# DB10005_CAN.net
KiCad netlist of a schematic drawn in Altium Designer
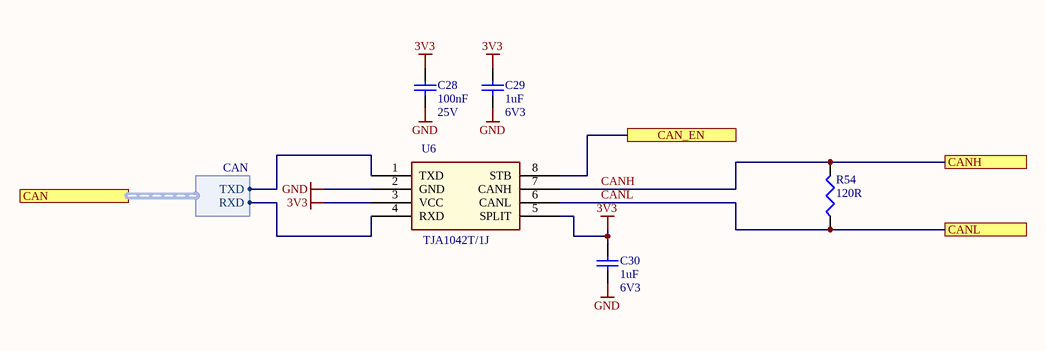
[diagram p0: DB10005_CAN.SchDoc]

(export (version "E")
  (design (tool "Eeschema 10.0.6"))
  (components
    (comp (ref "C28")
      (value "100nF")
      (footprint "C0402")
      (description "Capacitor, 100nF, 25V, X7R")
      (fields (field (name "VOLTAGE RATING") "25V"))
      (libsource (lib "AR_Capacitors_Ceramic") (part "100nF/0402/CER/25V"))
    )
    (comp (ref "C29")
      (value "1uF")
      (footprint "C0402")
      (description "Capacitor, 1uF, 6.3V, X5R")
      (fields (field (name "VOLTAGE RATING") "6V3"))
      (libsource (lib "AR_Capacitors_Ceramic") (part "1uF/0402/CER/6.3V"))
    )
    (comp (ref "C30")
      (value "1uF")
      (footprint "C0402")
      (description "Capacitor, 1uF, 6.3V, X5R")
      (fields (field (name "VOLTAGE RATING") "6V3"))
      (libsource (lib "AR_Capacitors_Ceramic") (part "1uF/0402/CER/6.3V"))
    )
    (comp (ref "R54")
      (value "120R")
      (footprint "0805")
      (description "Resistor, 0R, 0.1%, 0.1W, 150V, 200PPM, 0805")
      (libsource (lib "AR_Resistors_SMD") (part "0/0805/0100W/150V"))
    )
    (comp (ref "U6")
      (value "TJA1042T/1J")
      (footprint "SOP-8")
      (libsource (lib "DB10005_DieBieMS") (part "TJA1042T/1J"))
    )
  )
  (nets
    (net (code "2") (name "/CANH") (class "Default")
      (node (ref "R54") (pin "2") (pinfunction "2_2") (pintype "passive"))
      (node (ref "U6") (pin "7") (pinfunction "CANH_7") (pintype "passive"))
    )
    (net (code "3") (name "/CANL") (class "Default")
      (node (ref "R54") (pin "1") (pinfunction "1_1") (pintype "passive"))
      (node (ref "U6") (pin "6") (pinfunction "CANL_6") (pintype "passive"))
    )
    (net (code "4") (name "/CAN_EN") (class "Default")
      (node (ref "U6") (pin "8") (pinfunction "STB_8") (pintype "passive"))
    )
    (net (code "5") (name "/RXD") (class "Default")
      (node (ref "U6") (pin "4") (pinfunction "RXD_4") (pintype "passive"))
    )
    (net (code "6") (name "/TXD") (class "Default")
      (node (ref "U6") (pin "1") (pinfunction "TXD_1") (pintype "passive"))
    )
    (net (code "8") (name "3V3") (class "Default")
      (node (ref "C28") (pin "2") (pinfunction "2_2") (pintype "passive"))
      (node (ref "C29") (pin "2") (pinfunction "2_2") (pintype "passive"))
      (node (ref "C30") (pin "2") (pinfunction "2_2") (pintype "passive"))
      (node (ref "U6") (pin "3") (pinfunction "VCC_3") (pintype "passive"))
      (node (ref "U6") (pin "5") (pinfunction "SPLIT_5") (pintype "passive"))
    )
    (net (code "9") (name "GND") (class "Default")
      (node (ref "C28") (pin "1") (pinfunction "1_1") (pintype "passive"))
      (node (ref "C29") (pin "1") (pinfunction "1_1") (pintype "passive"))
      (node (ref "C30") (pin "1") (pinfunction "1_1") (pintype "passive"))
      (node (ref "U6") (pin "2") (pinfunction "GND_2") (pintype "passive"))
    )
  )
)
